# mcu.net
KiCad netlist of a schematic drawn in Altium Designer
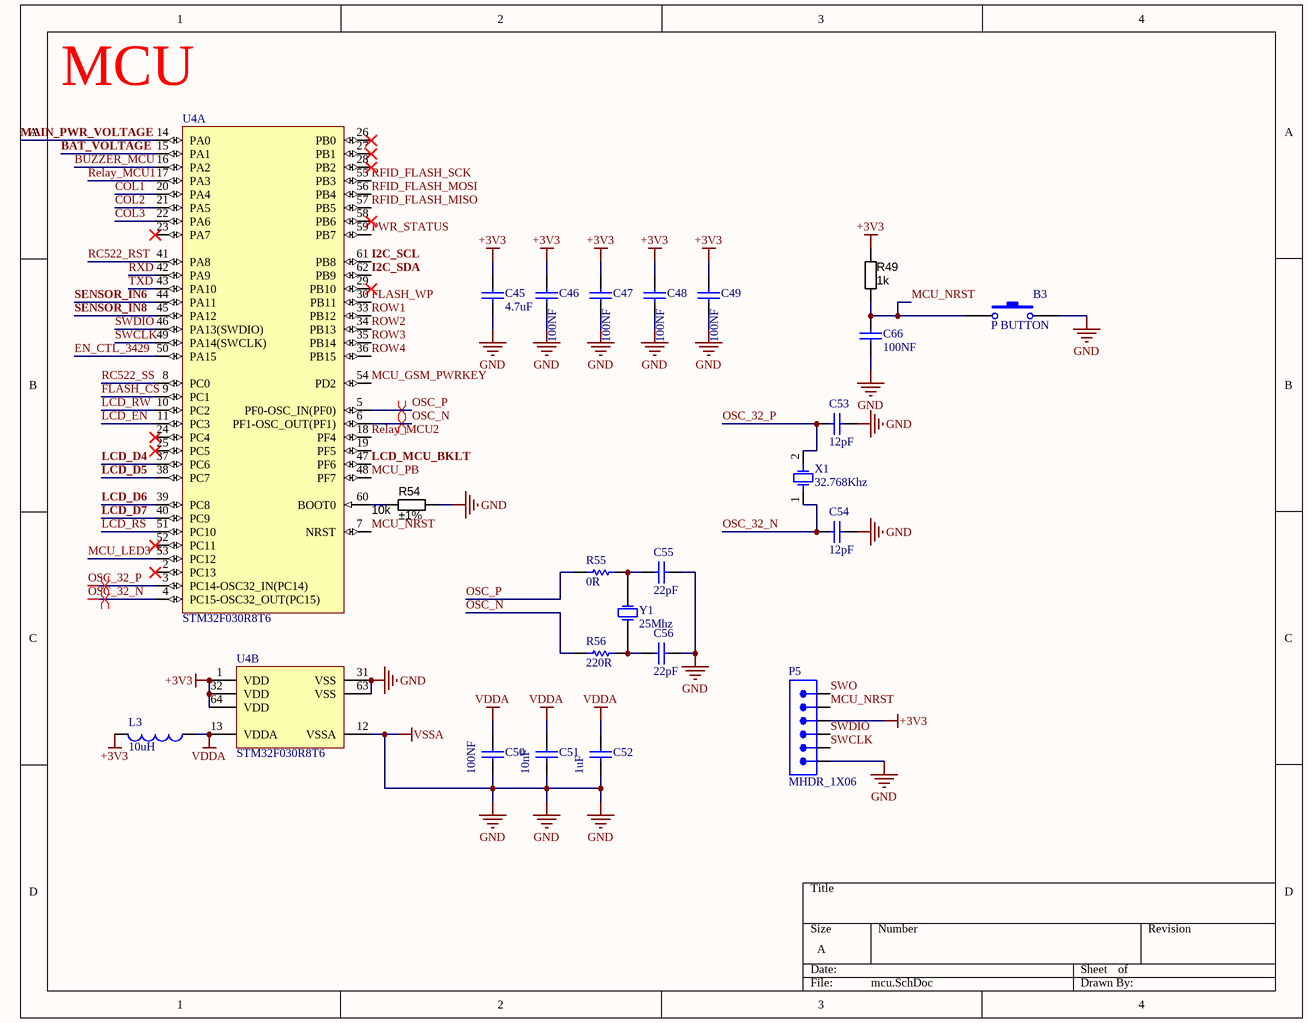
[diagram p0: mcu.SchDoc]

(export (version "E")
  (design (tool "Eeschema 10.0.6"))
  (components
    (comp (ref "B3")
      (value "P BUTTON")
      (footprint "MY_SPST-0.5")
      (libsource (lib "AMINLIB") (part "PUSH BUTTON_SMALL"))
    )
    (comp (ref "C45")
      (value "4.7uF")
      (footprint "MY_CAP_SMD_0603")
      (description "1.6 mm × 0.8 mm")
      (libsource (lib "AMINLIB") (part "CAP SMD_0603"))
    )
    (comp (ref "C46")
      (value "100NF")
      (footprint "CAP0603")
      (description "TOTAL CAPACITOR SMD PACK")
      (fields (field (name "DESIGNER") "Abbas Basereh"))
      (libsource (lib "Altium") (part "CAP SMD PACKAGE"))
    )
    (comp (ref "C47")
      (value "100NF")
      (footprint "CAP0603")
      (description "TOTAL CAPACITOR SMD PACK")
      (fields (field (name "DESIGNER") "Abbas Basereh"))
      (libsource (lib "Altium") (part "CAP SMD PACKAGE"))
    )
    (comp (ref "C48")
      (value "100NF")
      (footprint "CAP0603")
      (description "TOTAL CAPACITOR SMD PACK")
      (fields (field (name "DESIGNER") "Abbas Basereh"))
      (libsource (lib "Altium") (part "CAP SMD PACKAGE"))
    )
    (comp (ref "C49")
      (value "100NF")
      (footprint "CAP0603")
      (description "TOTAL CAPACITOR SMD PACK")
      (fields (field (name "DESIGNER") "Abbas Basereh"))
      (libsource (lib "Altium") (part "CAP SMD PACKAGE"))
    )
    (comp (ref "C50")
      (value "100NF")
      (footprint "CAP0603")
      (description "TOTAL CAPACITOR SMD PACK")
      (fields (field (name "DESIGNER") "Abbas Basereh"))
      (libsource (lib "Altium") (part "CAP SMD PACKAGE"))
    )
    (comp (ref "C51")
      (value "10nF")
      (footprint "MY_CAP_SMD_0603")
      (description "1.6 mm × 0.8 mm")
      (libsource (lib "AMINLIB") (part "CAP SMD_0603"))
    )
    (comp (ref "C52")
      (value "1uF")
      (footprint "MY_CAP_SMD_1206")
      (description "3.2 mm × 1.6 mm")
      (libsource (lib "altium-import") (part "root_1_CAP SMD_1206_"))
    )
    (comp (ref "C53")
      (value "12pF")
      (footprint "CAP0603")
      (description "TOTAL CAPACITOR SMD PACK")
      (fields (field (name "DESIGNER") "Abbas Basereh"))
      (libsource (lib "Altium") (part "CAP SMD PACKAGE"))
    )
    (comp (ref "C54")
      (value "12pF")
      (footprint "CAP0603")
      (description "TOTAL CAPACITOR SMD PACK")
      (fields (field (name "DESIGNER") "Abbas Basereh"))
      (libsource (lib "Altium") (part "CAP SMD PACKAGE"))
    )
    (comp (ref "C55")
      (value "22pF")
      (footprint "CAP0603")
      (description "TOTAL CAPACITOR SMD PACK")
      (fields (field (name "DESIGNER") "Abbas Basereh"))
      (libsource (lib "Altium") (part "CAP SMD PACKAGE"))
    )
    (comp (ref "C56")
      (value "22pF")
      (footprint "CAP0603")
      (description "TOTAL CAPACITOR SMD PACK")
      (fields (field (name "DESIGNER") "Abbas Basereh"))
      (libsource (lib "Altium") (part "CAP SMD PACKAGE"))
    )
    (comp (ref "C66")
      (value "100NF")
      (footprint "MY_CAP_SMD_0603")
      (description "1.6 mm × 0.8 mm")
      (libsource (lib "AMINLIB") (part "CAP SMD_0603"))
    )
    (comp (ref "L3")
      (value "10uH")
      (footprint "INDC3216")
      (description "Inductor")
      (fields (field (name "PUBLISHER") "Altium Limited"))
      (libsource (lib "altium-import") (part "root_2_Inductor_"))
    )
    (comp (ref "P5")
      (value "MHDR_1X06")
      (footprint "MHDR1X06-254P")
      (description "Male Header 1X06")
      (libsource (lib "SJ Sockets & Connectors") (part "MHDR_1X06"))
    )
    (comp (ref "R49")
      (value "1k")
      (footprint "RESC1608X55N")
      (description "Resistor SMD chip 1k Ohm 0.1W 1% 0603")
      (libsource (lib "Utiliti_Library") (part "RES_1K_0603_1%"))
    )
    (comp (ref "R54")
      (value "10k")
      (footprint "RESC1608X55N")
      (description "Resistor SMD chip 1k Ohm 0.1W 1% 0603")
      (fields (field (name "TOLERANCE") "±1%"))
      (libsource (lib "") (part "RES_1K_0603_1%_1"))
    )
    (comp (ref "R55")
      (value "0R")
      (footprint "R0603")
      (description "Resistor SMD 0603")
      (libsource (lib "Resistor") (part "Resistor SMD 0603"))
    )
    (comp (ref "R56")
      (value "220R")
      (footprint "R0603")
      (description "Resistor SMD 0603")
      (libsource (lib "Resistor") (part "Resistor SMD 0603"))
    )
    (comp (ref "U4")
      (value "STM32F030R8T6")
      (footprint "STM-LQFP64_N")
      (libsource (lib "STMicroelectronics STM32 F0") (part "STM32F030R8T6"))
    )
    (comp (ref "X1")
      (value "32.768Khz")
      (footprint "XTL_2_3215")
      (description "Crystal, 32.768KHz, 9pF, 20PPM")
      (libsource (lib "Practical") (part "Crystal 2 PIN"))
    )
    (comp (ref "Y1")
      (value "25Mhz")
      (footprint "Crystal SMD")
      (description "XTAL Crystal")
      (fields (field (name "DESIGNER") "ABBAS BASEREH"))
      (libsource (lib "2017AbbasBasereh9365731239 -ver1") (part "XTAL_Crystal"))
    )
  )
  (nets
    (net (code "1") (name "+3V3") (class "Default")
      (node (ref "C45") (pin "2") (pinfunction "2_2") (pintype "passive"))
      (node (ref "C46") (pin "2") (pinfunction "2_2") (pintype "passive"))
      (node (ref "C47") (pin "2") (pinfunction "2_2") (pintype "passive"))
      (node (ref "C48") (pin "2") (pinfunction "2_2") (pintype "passive"))
      (node (ref "C49") (pin "2") (pinfunction "2_2") (pintype "passive"))
      (node (ref "L3") (pin "2") (pinfunction "2_2") (pintype "passive"))
      (node (ref "P5") (pin "3") (pinfunction "3_3") (pintype "passive"))
      (node (ref "R49") (pin "2") (pinfunction "2_2") (pintype "passive"))
      (node (ref "U4") (pin "1") (pinfunction "VDD_1") (pintype "power_in"))
      (node (ref "U4") (pin "32") (pinfunction "VDD_32") (pintype "power_in"))
      (node (ref "U4") (pin "64") (pinfunction "VDD_64") (pintype "power_in"))
    )
    (net (code "2") (name "/BAT_VOLTAGE") (class "Default")
      (node (ref "U4") (pin "15") (pinfunction "PA1_15") (pintype "bidirectional"))
    )
    (net (code "3") (name "/BUZZER_MCU") (class "Default")
      (node (ref "U4") (pin "16") (pinfunction "PA2_16") (pintype "bidirectional"))
    )
    (net (code "4") (name "/COL1") (class "Default")
      (node (ref "U4") (pin "20") (pinfunction "PA4_20") (pintype "bidirectional"))
    )
    (net (code "5") (name "/COL2") (class "Default")
      (node (ref "U4") (pin "21") (pinfunction "PA5_21") (pintype "bidirectional"))
    )
    (net (code "6") (name "/COL3") (class "Default")
      (node (ref "U4") (pin "22") (pinfunction "PA6_22") (pintype "bidirectional"))
    )
    (net (code "7") (name "/EN_CTL_3429") (class "Default")
      (node (ref "U4") (pin "50") (pinfunction "PA15_50") (pintype "bidirectional"))
    )
    (net (code "8") (name "/FLASH_CS") (class "Default")
      (node (ref "U4") (pin "9") (pinfunction "PC1_9") (pintype "bidirectional"))
    )
    (net (code "9") (name "/FLASH_WP") (class "Default")
      (node (ref "U4") (pin "30") (pinfunction "PB11_30") (pintype "bidirectional"))
    )
    (net (code "10") (name "/I2C_SCL") (class "Default")
      (node (ref "U4") (pin "61") (pinfunction "PB8_61") (pintype "bidirectional"))
    )
    (net (code "11") (name "/I2C_SDA") (class "Default")
      (node (ref "U4") (pin "62") (pinfunction "PB9_62") (pintype "bidirectional"))
    )
    (net (code "12") (name "/LCD_D4") (class "Default")
      (node (ref "U4") (pin "37") (pinfunction "PC6_37") (pintype "bidirectional"))
    )
    (net (code "13") (name "/LCD_D5") (class "Default")
      (node (ref "U4") (pin "38") (pinfunction "PC7_38") (pintype "bidirectional"))
    )
    (net (code "14") (name "/LCD_D6") (class "Default")
      (node (ref "U4") (pin "39") (pinfunction "PC8_39") (pintype "bidirectional"))
    )
    (net (code "15") (name "/LCD_D7") (class "Default")
      (node (ref "U4") (pin "40") (pinfunction "PC9_40") (pintype "bidirectional"))
    )
    (net (code "16") (name "/LCD_EN") (class "Default")
      (node (ref "U4") (pin "11") (pinfunction "PC3_11") (pintype "bidirectional"))
    )
    (net (code "17") (name "/LCD_MCU_BKLT") (class "Default")
      (node (ref "U4") (pin "47") (pinfunction "PF6_47") (pintype "bidirectional"))
    )
    (net (code "18") (name "/LCD_RS") (class "Default")
      (node (ref "U4") (pin "51") (pinfunction "PC10_51") (pintype "bidirectional"))
    )
    (net (code "19") (name "/LCD_RW") (class "Default")
      (node (ref "U4") (pin "10") (pinfunction "PC2_10") (pintype "bidirectional"))
    )
    (net (code "20") (name "/MAIN_PWR_VOLTAGE") (class "Default")
      (node (ref "U4") (pin "14") (pinfunction "PA0_14") (pintype "bidirectional"))
    )
    (net (code "21") (name "/MCU_GSM_PWRKEY") (class "Default")
      (node (ref "U4") (pin "54") (pinfunction "PD2_54") (pintype "bidirectional"))
    )
    (net (code "22") (name "/MCU_LED3") (class "Default")
      (node (ref "U4") (pin "53") (pinfunction "PC12_53") (pintype "bidirectional"))
    )
    (net (code "23") (name "/MCU_NRST") (class "Default")
      (node (ref "B3") (pin "1") (pinfunction "1_1") (pintype "passive"))
      (node (ref "C66") (pin "2") (pinfunction "2_2") (pintype "passive"))
      (node (ref "P5") (pin "2") (pinfunction "2_2") (pintype "passive"))
      (node (ref "R49") (pin "1") (pinfunction "1_1") (pintype "passive"))
      (node (ref "U4") (pin "7") (pinfunction "NRST_7") (pintype "bidirectional"))
    )
    (net (code "24") (name "/MCU_PB") (class "Default")
      (node (ref "U4") (pin "48") (pinfunction "PF7_48") (pintype "bidirectional"))
    )
    (net (code "25") (name "/OSC_32_N") (class "Default")
      (node (ref "C54") (pin "2") (pinfunction "2_2") (pintype "passive"))
      (node (ref "U4") (pin "4") (pinfunction "PC15-OSC32_OUT(PC15)_4") (pintype "bidirectional"))
      (node (ref "X1") (pin "1") (pinfunction "OSC1_1") (pintype "passive"))
    )
    (net (code "26") (name "/OSC_32_P") (class "Default")
      (node (ref "C53") (pin "2") (pinfunction "2_2") (pintype "passive"))
      (node (ref "U4") (pin "3") (pinfunction "PC14-OSC32_IN(PC14)_3") (pintype "bidirectional"))
      (node (ref "X1") (pin "2") (pinfunction "OSC2_2") (pintype "passive"))
    )
    (net (code "27") (name "/OSC_N") (class "Default")
      (node (ref "R56") (pin "2") (pinfunction "2_2") (pintype "passive"))
      (node (ref "U4") (pin "6") (pinfunction "PF1-OSC_OUT(PF1)_6") (pintype "bidirectional"))
    )
    (net (code "28") (name "/OSC_P") (class "Default")
      (node (ref "R55") (pin "2") (pinfunction "2_2") (pintype "passive"))
      (node (ref "U4") (pin "5") (pinfunction "PF0-OSC_IN(PF0)_5") (pintype "bidirectional"))
    )
    (net (code "29") (name "/PWR_STATUS") (class "Default")
      (node (ref "U4") (pin "59") (pinfunction "PB7_59") (pintype "bidirectional"))
    )
    (net (code "30") (name "/RC522_RST") (class "Default")
      (node (ref "U4") (pin "41") (pinfunction "PA8_41") (pintype "bidirectional"))
    )
    (net (code "31") (name "/RC522_SS") (class "Default")
      (node (ref "U4") (pin "8") (pinfunction "PC0_8") (pintype "bidirectional"))
    )
    (net (code "32") (name "/RFID_FLASH_MISO") (class "Default")
      (node (ref "U4") (pin "57") (pinfunction "PB5_57") (pintype "bidirectional"))
    )
    (net (code "33") (name "/RFID_FLASH_MOSI") (class "Default")
      (node (ref "U4") (pin "56") (pinfunction "PB4_56") (pintype "bidirectional"))
    )
    (net (code "34") (name "/RFID_FLASH_SCK") (class "Default")
      (node (ref "U4") (pin "55") (pinfunction "PB3_55") (pintype "bidirectional"))
    )
    (net (code "35") (name "/ROW1") (class "Default")
      (node (ref "U4") (pin "33") (pinfunction "PB12_33") (pintype "bidirectional"))
    )
    (net (code "36") (name "/ROW2") (class "Default")
      (node (ref "U4") (pin "34") (pinfunction "PB13_34") (pintype "bidirectional"))
    )
    (net (code "37") (name "/ROW3") (class "Default")
      (node (ref "U4") (pin "35") (pinfunction "PB14_35") (pintype "bidirectional"))
    )
    (net (code "38") (name "/ROW4") (class "Default")
      (node (ref "U4") (pin "36") (pinfunction "PB15_36") (pintype "bidirectional"))
    )
    (net (code "39") (name "/RXD") (class "Default")
      (node (ref "U4") (pin "42") (pinfunction "PA9_42") (pintype "bidirectional"))
    )
    (net (code "40") (name "/Relay_MCU1") (class "Default")
      (node (ref "U4") (pin "17") (pinfunction "PA3_17") (pintype "bidirectional"))
    )
    (net (code "41") (name "/Relay_MCU2") (class "Default")
      (node (ref "U4") (pin "18") (pinfunction "PF4_18") (pintype "bidirectional"))
    )
    (net (code "42") (name "/SENSOR_IN6") (class "Default")
      (node (ref "U4") (pin "44") (pinfunction "PA11_44") (pintype "bidirectional"))
    )
    (net (code "43") (name "/SENSOR_IN8") (class "Default")
      (node (ref "U4") (pin "45") (pinfunction "PA12_45") (pintype "bidirectional"))
    )
    (net (code "44") (name "/SWCLK") (class "Default")
      (node (ref "P5") (pin "5") (pinfunction "5_5") (pintype "passive"))
      (node (ref "U4") (pin "49") (pinfunction "PA14(SWCLK)_49") (pintype "bidirectional"))
    )
    (net (code "45") (name "/SWDIO") (class "Default")
      (node (ref "P5") (pin "4") (pinfunction "4_4") (pintype "passive"))
      (node (ref "U4") (pin "46") (pinfunction "PA13(SWDIO)_46") (pintype "bidirectional"))
    )
    (net (code "46") (name "/SWO") (class "Default")
      (node (ref "P5") (pin "1") (pinfunction "1_1") (pintype "passive"))
    )
    (net (code "47") (name "/TXD") (class "Default")
      (node (ref "U4") (pin "43") (pinfunction "PA10_43") (pintype "bidirectional"))
    )
    (net (code "48") (name "GND") (class "Default")
      (node (ref "B3") (pin "2") (pinfunction "2_2") (pintype "passive"))
      (node (ref "C45") (pin "1") (pinfunction "1_1") (pintype "passive"))
      (node (ref "C46") (pin "1") (pinfunction "1_1") (pintype "passive"))
      (node (ref "C47") (pin "1") (pinfunction "1_1") (pintype "passive"))
      (node (ref "C48") (pin "1") (pinfunction "1_1") (pintype "passive"))
      (node (ref "C49") (pin "1") (pinfunction "1_1") (pintype "passive"))
      (node (ref "C50") (pin "1") (pinfunction "1_1") (pintype "passive"))
      (node (ref "C51") (pin "1") (pinfunction "1_1") (pintype "passive"))
      (node (ref "C52") (pin "1") (pinfunction "1_1") (pintype "passive"))
      (node (ref "C53") (pin "1") (pinfunction "1_1") (pintype "passive"))
      (node (ref "C54") (pin "1") (pinfunction "1_1") (pintype "passive"))
      (node (ref "C55") (pin "1") (pinfunction "1_1") (pintype "passive"))
      (node (ref "C56") (pin "1") (pinfunction "1_1") (pintype "passive"))
      (node (ref "C66") (pin "1") (pinfunction "1_1") (pintype "passive"))
      (node (ref "P5") (pin "6") (pinfunction "6_6") (pintype "passive"))
      (node (ref "R54") (pin "2") (pinfunction "2_2") (pintype "passive"))
      (node (ref "U4") (pin "12") (pinfunction "VSSA_12") (pintype "power_in"))
      (node (ref "U4") (pin "31") (pinfunction "VSS_31") (pintype "power_in"))
      (node (ref "U4") (pin "63") (pinfunction "VSS_63") (pintype "power_in"))
    )
    (net (code "49") (name "Net-(U4A-BOOT0)") (class "Default")
      (node (ref "R54") (pin "1") (pinfunction "1_1") (pintype "passive"))
      (node (ref "U4") (pin "60") (pinfunction "BOOT0_60") (pintype "input"))
    )
    (net (code "50") (name "Net-(Y1-OSC1)") (class "Default")
      (node (ref "C56") (pin "2") (pinfunction "2_2") (pintype "passive"))
      (node (ref "R56") (pin "1") (pinfunction "1_1") (pintype "passive"))
      (node (ref "Y1") (pin "1") (pinfunction "OSC1_1") (pintype "passive"))
    )
    (net (code "51") (name "Net-(Y1-OSC2)") (class "Default")
      (node (ref "C55") (pin "2") (pinfunction "2_2") (pintype "passive"))
      (node (ref "R55") (pin "1") (pinfunction "1_1") (pintype "passive"))
      (node (ref "Y1") (pin "2") (pinfunction "OSC2_2") (pintype "passive"))
    )
    (net (code "52") (name "VDDA") (class "Default")
      (node (ref "C50") (pin "2") (pinfunction "2_2") (pintype "passive"))
      (node (ref "C51") (pin "2") (pinfunction "2_2") (pintype "passive"))
      (node (ref "C52") (pin "2") (pinfunction "2_2") (pintype "passive"))
      (node (ref "L3") (pin "1") (pinfunction "1_1") (pintype "passive"))
      (node (ref "U4") (pin "13") (pinfunction "VDDA_13") (pintype "power_in"))
    )
    (net (code "53") (name "unconnected-(U4A-PA7-Pad23)") (class "Default")
      (node (ref "U4") (pin "23") (pinfunction "PA7_23") (pintype "bidirectional+no_connect"))
    )
    (net (code "54") (name "unconnected-(U4A-PB0-Pad26)") (class "Default")
      (node (ref "U4") (pin "26") (pinfunction "PB0_26") (pintype "bidirectional+no_connect"))
    )
    (net (code "55") (name "unconnected-(U4A-PB1-Pad27)") (class "Default")
      (node (ref "U4") (pin "27") (pinfunction "PB1_27") (pintype "bidirectional+no_connect"))
    )
    (net (code "56") (name "unconnected-(U4A-PB2-Pad28)") (class "Default")
      (node (ref "U4") (pin "28") (pinfunction "PB2_28") (pintype "bidirectional+no_connect"))
    )
    (net (code "57") (name "unconnected-(U4A-PB6-Pad58)") (class "Default")
      (node (ref "U4") (pin "58") (pinfunction "PB6_58") (pintype "bidirectional+no_connect"))
    )
    (net (code "58") (name "unconnected-(U4A-PB10-Pad29)") (class "Default")
      (node (ref "U4") (pin "29") (pinfunction "PB10_29") (pintype "bidirectional+no_connect"))
    )
    (net (code "59") (name "unconnected-(U4A-PC4-Pad24)") (class "Default")
      (node (ref "U4") (pin "24") (pinfunction "PC4_24") (pintype "bidirectional+no_connect"))
    )
    (net (code "60") (name "unconnected-(U4A-PC5-Pad25)") (class "Default")
      (node (ref "U4") (pin "25") (pinfunction "PC5_25") (pintype "bidirectional+no_connect"))
    )
    (net (code "61") (name "unconnected-(U4A-PC11-Pad52)") (class "Default")
      (node (ref "U4") (pin "52") (pinfunction "PC11_52") (pintype "bidirectional+no_connect"))
    )
    (net (code "62") (name "unconnected-(U4A-PC13-Pad2)") (class "Default")
      (node (ref "U4") (pin "2") (pinfunction "PC13_2") (pintype "bidirectional+no_connect"))
    )
    (net (code "63") (name "unconnected-(U4A-PF5-Pad19)") (class "Default")
      (node (ref "U4") (pin "19") (pinfunction "PF5_19") (pintype "bidirectional"))
    )
  )
)
